# design.net
KiCad netlist of a schematic drawn in Altium Designer
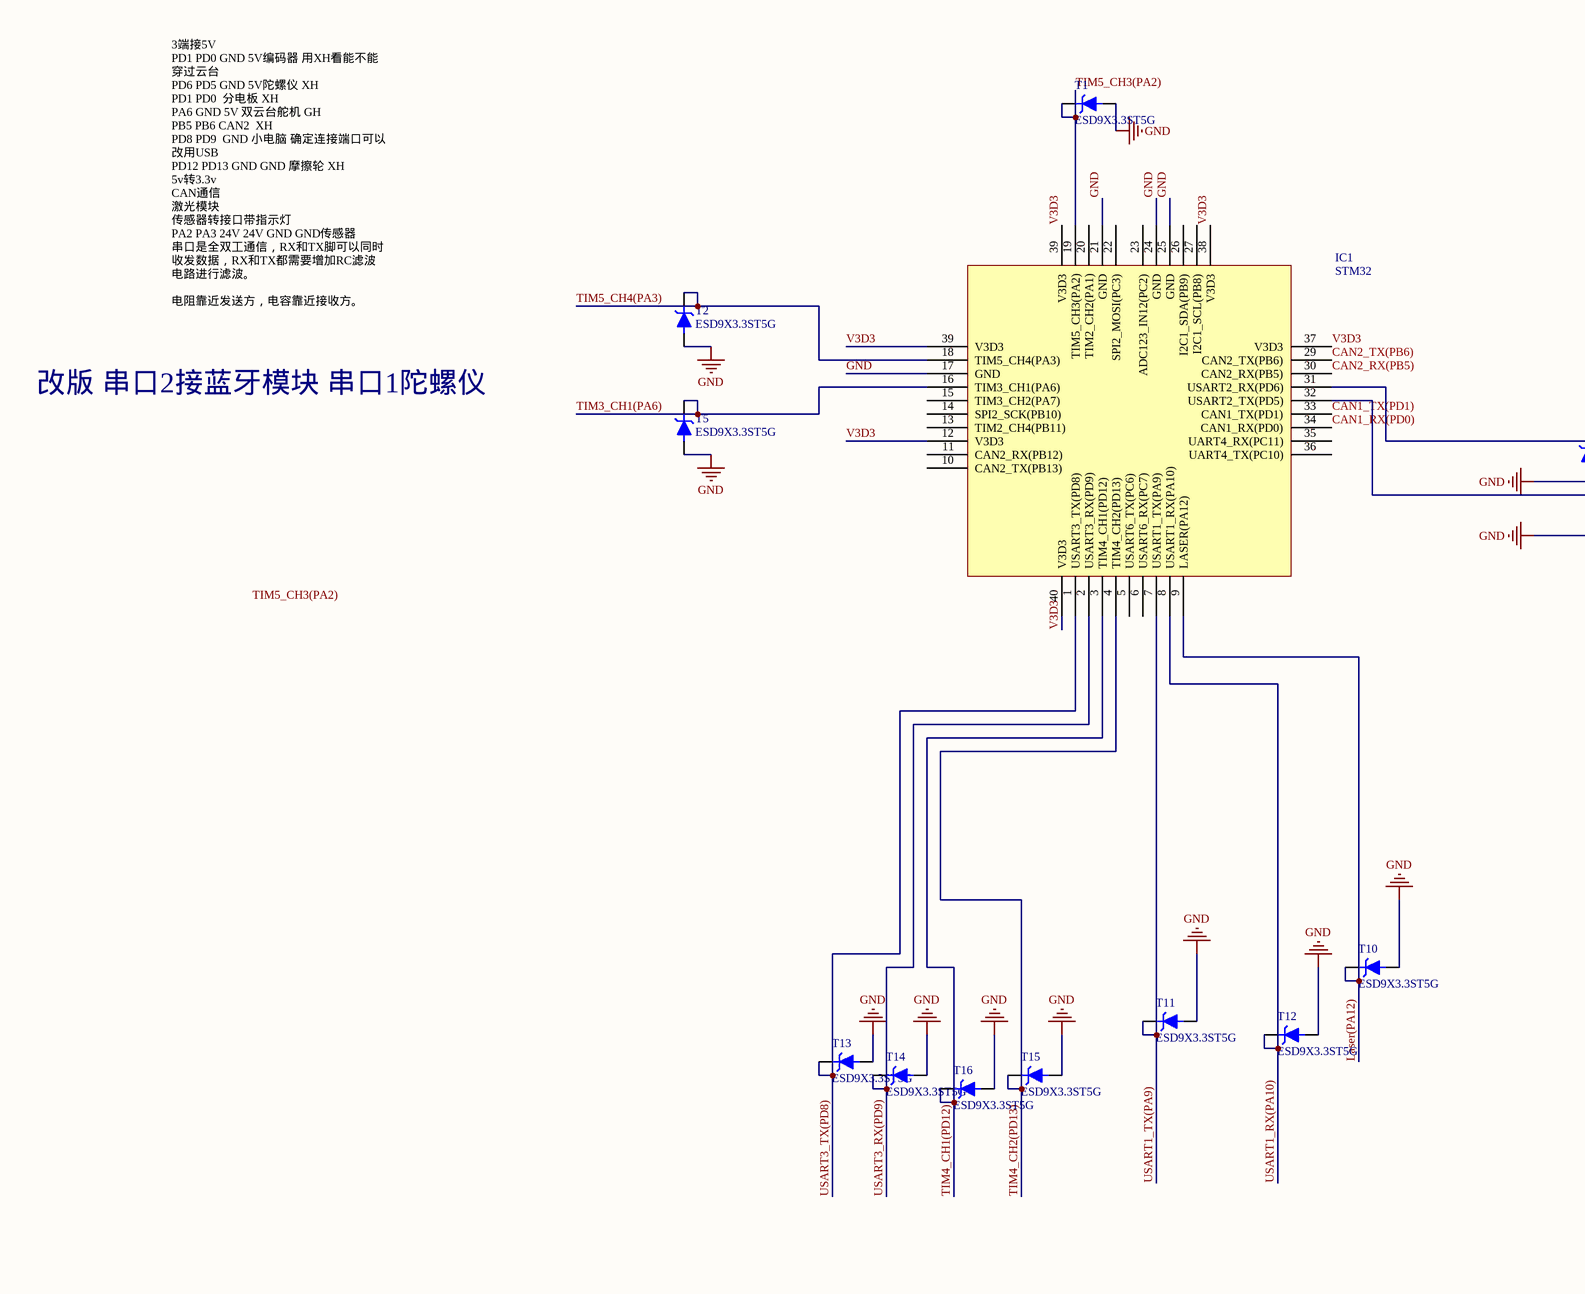
[diagram p0: 云台扩展板.SchDoc, left]
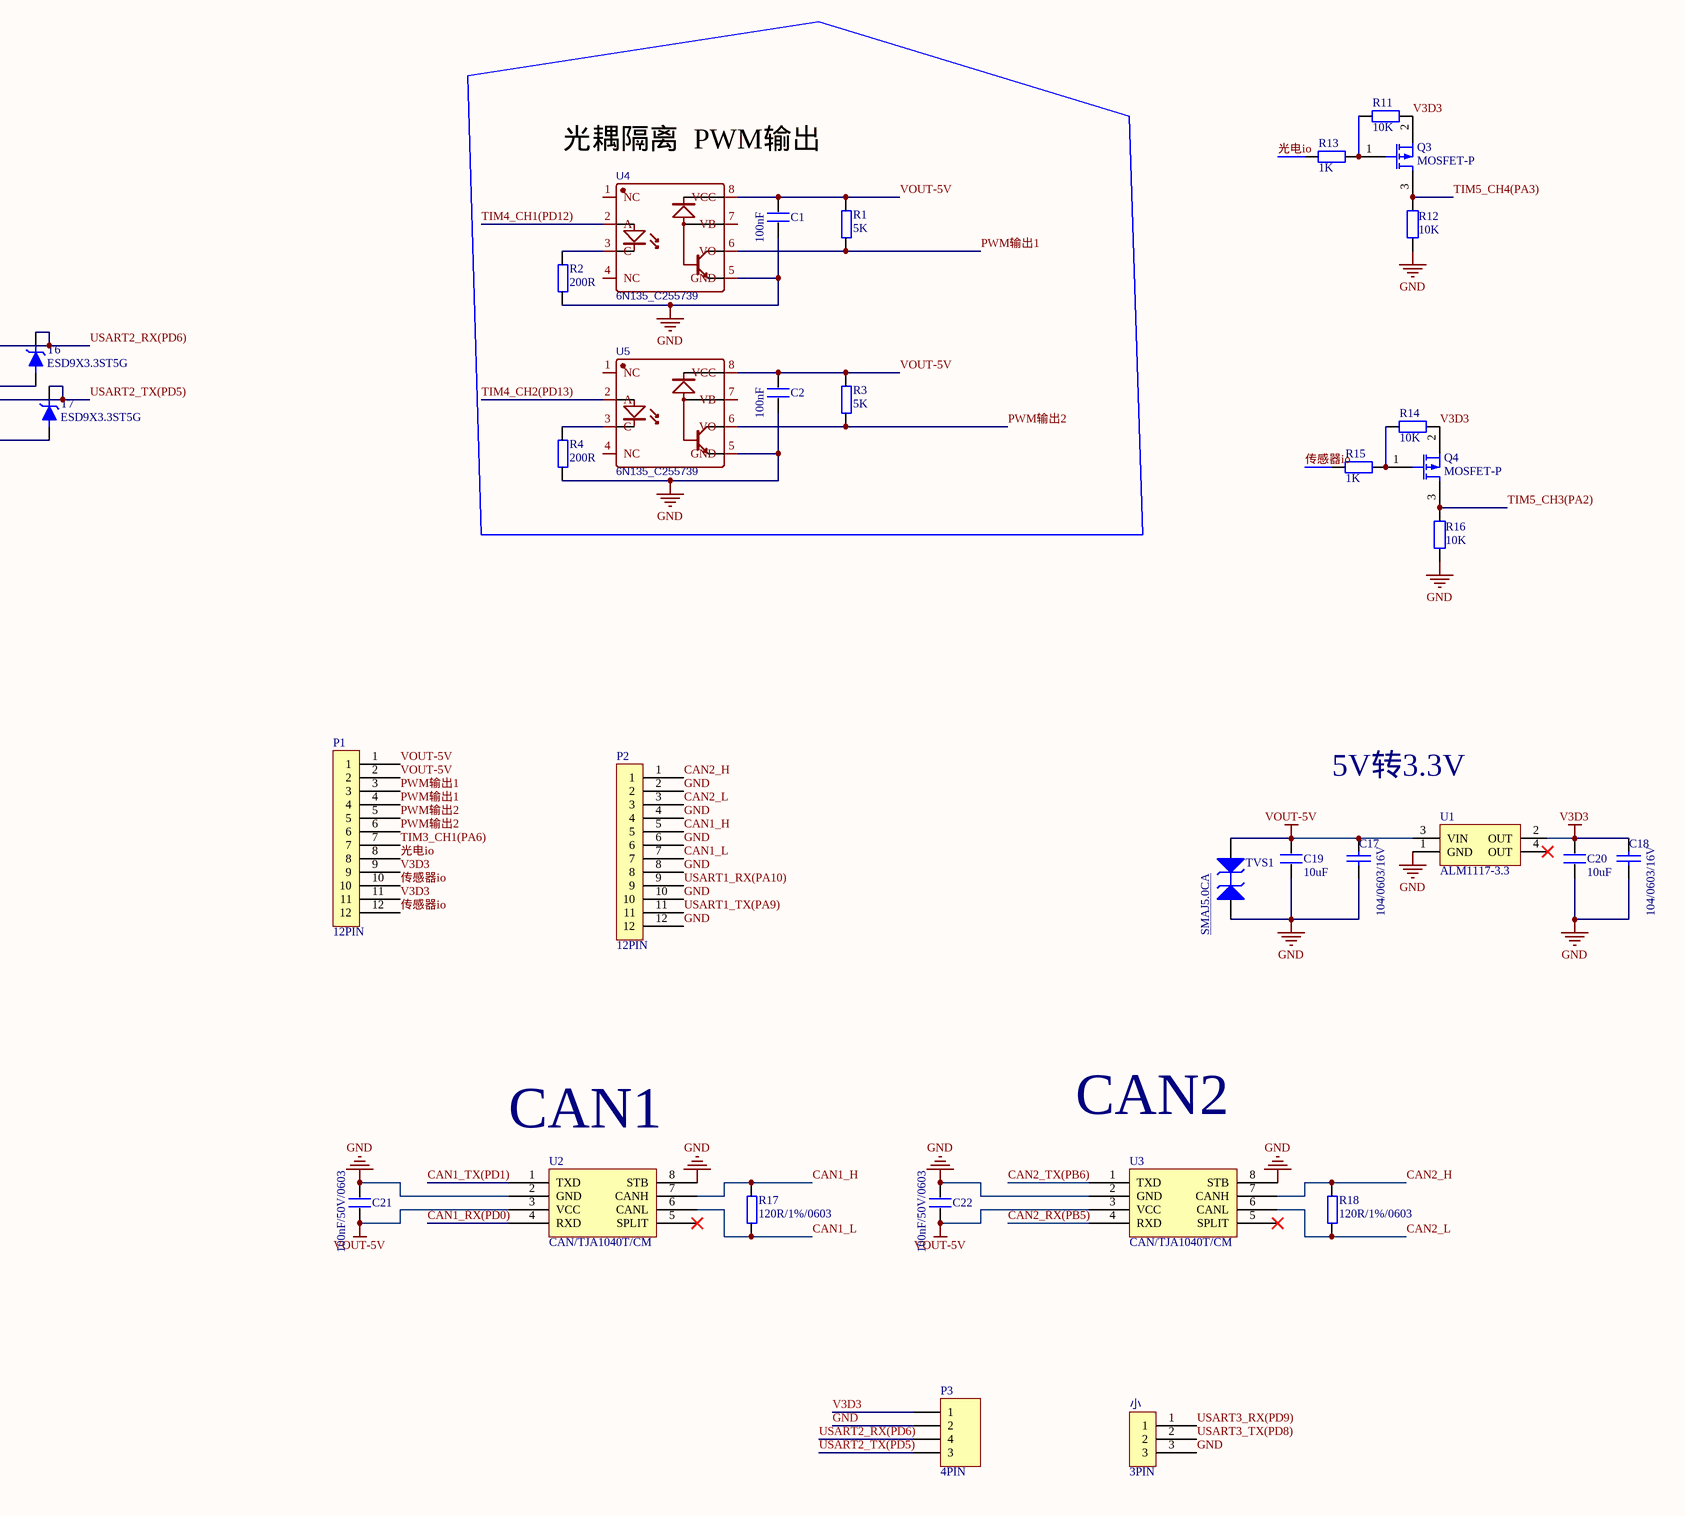
[diagram p1: 云台扩展板.SchDoc, right]

(export (version "E")
  (design (tool "Eeschema 10.0.6"))
  (components
    (comp (ref "C1") (value "100nF") (footprint "0603_C") (libsource (lib "Robotmaster") (part "C")))
    (comp (ref "C2") (value "100nF") (footprint "0603_C") (libsource (lib "Robotmaster") (part "C")))
    (comp (ref "C17")
      (value "104/0603/16V")
      (footprint "C0805")
      (fields (field (name "ALTIUM_UNNAMED_1") "104/0603/16V"))
      (libsource (lib "Common Device") (part "CAP"))
    )
    (comp (ref "C18")
      (value "104/0603/16V")
      (footprint "C0805")
      (fields (field (name "ALTIUM_UNNAMED_1") "104/0603/16V"))
      (libsource (lib "Common Device") (part "CAP"))
    )
    (comp (ref "C19") (value "10uF") (footprint "C0805") (libsource (lib "Robotmaster") (part "C")))
    (comp (ref "C20") (value "10uF") (footprint "C0805") (libsource (lib "Robotmaster") (part "C")))
    (comp (ref "C21") (value "100nF/50V/0603") (footprint "C0805") (libsource (lib "Robotmaster") (part "C")))
    (comp (ref "C22") (value "100nF/50V/0603") (footprint "C0805") (libsource (lib "Robotmaster") (part "C")))
    (comp (ref "IC1") (value "STM32") (footprint "STM") (libsource (lib "PP_SCHlib_Altium") (part "STM32_1")))
    (comp (ref "P1") (value "12PIN") (footprint "12pin") (libsource (lib "更多原理图库") (part "12PIN")))
    (comp (ref "P2") (value "12PIN") (footprint "12pin") (libsource (lib "更多原理图库") (part "12PIN")))
    (comp (ref "P3")
      (value "4PIN")
      (footprint "HDR1X4")
      (description "Header, 4-Pin")
      (fields (field (name "PUBLISHER") "Altium Limited"))
      (libsource (lib "Miscellaneous Connectors") (part "Header 4"))
    )
    (comp (ref "Q3")
      (value "MOSFET-P")
      (footprint "SOT-23(SOT-23-3)")
      (libsource (lib "我的库1.1") (part "MOSFET-P"))
    )
    (comp (ref "Q4")
      (value "MOSFET-P")
      (footprint "SOT-23(SOT-23-3)")
      (libsource (lib "我的库1.1") (part "MOSFET-P"))
    )
    (comp (ref "R1") (value "5K") (footprint "0603_R") (libsource (lib "Robotmaster") (part "R")))
    (comp (ref "R2") (value "200R") (footprint "0603_R") (libsource (lib "Robotmaster") (part "R")))
    (comp (ref "R3") (value "5K") (footprint "0603_R") (libsource (lib "Robotmaster") (part "R")))
    (comp (ref "R4") (value "200R") (footprint "0603_R") (libsource (lib "Robotmaster") (part "R")))
    (comp (ref "R11")
      (value "10K")
      (footprint "0603_R")
      (description "Resistor")
      (fields (field (name "Comment") "Res2"))
      (libsource (lib "我的库") (part "Res2"))
    )
    (comp (ref "R12")
      (value "10K")
      (footprint "0603_R")
      (description "Resistor")
      (fields (field (name "Comment") "Res2"))
      (libsource (lib "") (part "Res2_1"))
    )
    (comp (ref "R13")
      (value "1K")
      (footprint "0603_R")
      (description "Resistor")
      (fields (field (name "Comment") "Res2"))
      (libsource (lib "我的库") (part "Res2"))
    )
    (comp (ref "R14")
      (value "10K")
      (footprint "0603_R")
      (description "Resistor")
      (fields (field (name "Comment") "Res2"))
      (libsource (lib "我的库") (part "Res2"))
    )
    (comp (ref "R15")
      (value "1K")
      (footprint "0603_R")
      (description "Resistor")
      (fields (field (name "Comment") "Res2"))
      (libsource (lib "我的库") (part "Res2"))
    )
    (comp (ref "R16")
      (value "10K")
      (footprint "0603_R")
      (description "Resistor")
      (fields (field (name "Comment") "Res2"))
      (libsource (lib "") (part "Res2_1"))
    )
    (comp (ref "R17") (value "120R/1%/0603") (footprint "0603 R") (libsource (lib "Robotmaster") (part "R")))
    (comp (ref "R18") (value "120R/1%/0603") (footprint "0603 R") (libsource (lib "Robotmaster") (part "R")))
    (comp (ref "T1")
      (value "ESD9X3.3ST5G")
      (footprint "ESD9X3.3ST5G")
      (libsource (lib "PP_SCHlib_Altium") (part "TVS"))
    )
    (comp (ref "T2")
      (value "ESD9X3.3ST5G")
      (footprint "ESD9X3.3ST5G")
      (libsource (lib "PP_SCHlib_Altium") (part "TVS"))
    )
    (comp (ref "T5")
      (value "ESD9X3.3ST5G")
      (footprint "ESD9X3.3ST5G")
      (libsource (lib "PP_SCHlib_Altium") (part "TVS"))
    )
    (comp (ref "T6")
      (value "ESD9X3.3ST5G")
      (footprint "ESD9X3.3ST5G")
      (libsource (lib "PP_SCHlib_Altium") (part "TVS"))
    )
    (comp (ref "T7")
      (value "ESD9X3.3ST5G")
      (footprint "ESD9X3.3ST5G")
      (libsource (lib "PP_SCHlib_Altium") (part "TVS"))
    )
    (comp (ref "T10")
      (value "ESD9X3.3ST5G")
      (footprint "ESD9X3.3ST5G")
      (libsource (lib "PP_SCHlib_Altium") (part "TVS"))
    )
    (comp (ref "T11")
      (value "ESD9X3.3ST5G")
      (footprint "ESD9X3.3ST5G")
      (libsource (lib "PP_SCHlib_Altium") (part "TVS"))
    )
    (comp (ref "T12")
      (value "ESD9X3.3ST5G")
      (footprint "ESD9X3.3ST5G")
      (libsource (lib "PP_SCHlib_Altium") (part "TVS"))
    )
    (comp (ref "T13")
      (value "ESD9X3.3ST5G")
      (footprint "ESD9X3.3ST5G")
      (libsource (lib "PP_SCHlib_Altium") (part "TVS"))
    )
    (comp (ref "T14")
      (value "ESD9X3.3ST5G")
      (footprint "ESD9X3.3ST5G")
      (libsource (lib "PP_SCHlib_Altium") (part "TVS"))
    )
    (comp (ref "T15")
      (value "ESD9X3.3ST5G")
      (footprint "ESD9X3.3ST5G")
      (libsource (lib "PP_SCHlib_Altium") (part "TVS"))
    )
    (comp (ref "T16")
      (value "ESD9X3.3ST5G")
      (footprint "ESD9X3.3ST5G")
      (libsource (lib "PP_SCHlib_Altium") (part "TVS"))
    )
    (comp (ref "TVS1")
      (value "SMAJ5.0CA")
      (footprint "SMA(DO-214AC)_S1")
      (libsource (lib "VL53L0X激光测距传感器模块") (part "TVS"))
    )
    (comp (ref "U1")
      (value "ALM1117-3.3")
      (footprint "SOT-223")
      (libsource (lib "Robotmaster") (part "LM1117-3.3"))
    )
    (comp (ref "U2")
      (value "CAN/TJA1040T/CM")
      (footprint "CAN/TJA1040T/CM")
      (description "CAN")
      (libsource (lib "Miscellaneous Devices LC") (part "CAN/TJA1040T/CM_[C6951]"))
    )
    (comp (ref "U3")
      (value "CAN/TJA1040T/CM")
      (footprint "CAN/TJA1040T/CM")
      (description "CAN")
      (libsource (lib "Miscellaneous Devices LC") (part "CAN/TJA1040T/CM_[C6951]"))
    )
    (comp (ref "U4")
      (value "6N135_C255739")
      (footprint "DIP-8")
      (fields
        (field (name "BOM_SUPPLIER PART") "C255739")
        (field (name "BOM_MANUFACTURER PART") "6N135")
        (field (name "CONTRIBUTOR") "LCSC")
      )
      (libsource (lib "我的库") (part "6N135_C255739"))
    )
    (comp (ref "U5")
      (value "6N135_C255739")
      (footprint "DIP-8")
      (fields
        (field (name "BOM_SUPPLIER PART") "C255739")
        (field (name "BOM_MANUFACTURER PART") "6N135")
        (field (name "CONTRIBUTOR") "LCSC")
      )
      (libsource (lib "我的库") (part "6N135_C255739"))
    )
    (comp (ref "小") (value "3PIN") (footprint "XH2.54-3") (libsource (lib "PP_SCHlib_Altium") (part "3PIN")))
  )
  (nets
    (net (code "1") (name "/CAN1_H") (class "Default")
      (node (ref "P2") (pin "5") (pinfunction "5_5") (pintype "passive"))
      (node (ref "R17") (pin "2") (pintype "passive"))
      (node (ref "U2") (pin "7") (pinfunction "CANH_7") (pintype "passive"))
    )
    (net (code "2") (name "/CAN1_L") (class "Default")
      (node (ref "P2") (pin "7") (pinfunction "7_7") (pintype "passive"))
      (node (ref "R17") (pin "1") (pintype "passive"))
      (node (ref "U2") (pin "6") (pinfunction "CANL_6") (pintype "passive"))
    )
    (net (code "3") (name "/CAN1_RX(PD0)") (class "Default")
      (node (ref "IC1") (pin "34") (pinfunction "CAN1_RX(PD0)_34") (pintype "passive"))
      (node (ref "U2") (pin "4") (pinfunction "RXD_4") (pintype "passive"))
    )
    (net (code "4") (name "/CAN1_TX(PD1)") (class "Default")
      (node (ref "IC1") (pin "33") (pinfunction "CAN1_TX(PD1)_33") (pintype "passive"))
      (node (ref "U2") (pin "1") (pinfunction "TXD_1") (pintype "passive"))
    )
    (net (code "5") (name "/CAN2_H") (class "Default")
      (node (ref "P2") (pin "1") (pinfunction "1_1") (pintype "passive"))
      (node (ref "R18") (pin "2") (pintype "passive"))
      (node (ref "U3") (pin "7") (pinfunction "CANH_7") (pintype "passive"))
    )
    (net (code "6") (name "/CAN2_L") (class "Default")
      (node (ref "P2") (pin "3") (pinfunction "3_3") (pintype "passive"))
      (node (ref "R18") (pin "1") (pintype "passive"))
      (node (ref "U3") (pin "6") (pinfunction "CANL_6") (pintype "passive"))
    )
    (net (code "7") (name "/CAN2_RX(PB5)") (class "Default")
      (node (ref "IC1") (pin "30") (pinfunction "CAN2_RX(PB5)_30") (pintype "passive"))
      (node (ref "U3") (pin "4") (pinfunction "RXD_4") (pintype "passive"))
    )
    (net (code "8") (name "/CAN2_TX(PB6)") (class "Default")
      (node (ref "IC1") (pin "29") (pinfunction "CAN2_TX(PB6)_29") (pintype "passive"))
      (node (ref "U3") (pin "1") (pinfunction "TXD_1") (pintype "passive"))
    )
    (net (code "9") (name "/Laser(PA12)") (class "Default")
      (node (ref "IC1") (pin "9") (pinfunction "LASER(PA12)_9") (pintype "passive"))
      (node (ref "T10") (pin "2") (pinfunction "K_2") (pintype "passive"))
    )
    (net (code "10") (name "/PWM输出1") (class "Default")
      (node (ref "P1") (pin "3") (pinfunction "3_3") (pintype "passive"))
      (node (ref "P1") (pin "4") (pinfunction "4_4") (pintype "passive"))
      (node (ref "R1") (pin "1") (pintype "passive"))
      (node (ref "U4") (pin "6") (pinfunction "VO_6") (pintype "passive"))
    )
    (net (code "11") (name "/PWM输出2") (class "Default")
      (node (ref "P1") (pin "5") (pinfunction "5_5") (pintype "passive"))
      (node (ref "P1") (pin "6") (pinfunction "6_6") (pintype "passive"))
      (node (ref "R3") (pin "1") (pintype "passive"))
      (node (ref "U5") (pin "6") (pinfunction "VO_6") (pintype "passive"))
    )
    (net (code "12") (name "/TIM3_CH1(PA6)") (class "Default")
      (node (ref "IC1") (pin "16") (pinfunction "TIM3_CH1(PA6)_16") (pintype "passive"))
      (node (ref "P1") (pin "7") (pinfunction "7_7") (pintype "passive"))
      (node (ref "T5") (pin "2") (pinfunction "K_2") (pintype "passive"))
    )
    (net (code "13") (name "/TIM4_CH1(PD12)") (class "Default")
      (node (ref "IC1") (pin "3") (pinfunction "TIM4_CH1(PD12)_3") (pintype "passive"))
      (node (ref "T16") (pin "2") (pinfunction "K_2") (pintype "passive"))
      (node (ref "U4") (pin "2") (pinfunction "A_2") (pintype "passive"))
    )
    (net (code "14") (name "/TIM4_CH2(PD13)") (class "Default")
      (node (ref "IC1") (pin "4") (pinfunction "TIM4_CH2(PD13)_4") (pintype "passive"))
      (node (ref "T15") (pin "2") (pinfunction "K_2") (pintype "passive"))
      (node (ref "U5") (pin "2") (pinfunction "A_2") (pintype "passive"))
    )
    (net (code "15") (name "/TIM5_CH3(PA2)") (class "Default")
      (node (ref "IC1") (pin "19") (pinfunction "TIM5_CH3(PA2)_19") (pintype "passive"))
      (node (ref "Q4") (pin "3") (pinfunction "D_3") (pintype "passive"))
      (node (ref "R16") (pin "1") (pinfunction "1_1") (pintype "passive"))
      (node (ref "T1") (pin "2") (pinfunction "K_2") (pintype "passive"))
    )
    (net (code "16") (name "/TIM5_CH4(PA3)") (class "Default")
      (node (ref "IC1") (pin "18") (pinfunction "TIM5_CH4(PA3)_18") (pintype "passive"))
      (node (ref "Q3") (pin "3") (pinfunction "D_3") (pintype "passive"))
      (node (ref "R12") (pin "1") (pinfunction "1_1") (pintype "passive"))
      (node (ref "T2") (pin "2") (pinfunction "K_2") (pintype "passive"))
    )
    (net (code "17") (name "/USART1_RX(PA10)") (class "Default")
      (node (ref "IC1") (pin "8") (pinfunction "USART1_RX(PA10)_8") (pintype "passive"))
      (node (ref "P2") (pin "9") (pinfunction "9_9") (pintype "passive"))
      (node (ref "T12") (pin "2") (pinfunction "K_2") (pintype "passive"))
    )
    (net (code "18") (name "/USART1_TX(PA9)") (class "Default")
      (node (ref "IC1") (pin "7") (pinfunction "USART1_TX(PA9)_7") (pintype "passive"))
      (node (ref "P2") (pin "11") (pinfunction "11_11") (pintype "passive"))
      (node (ref "T11") (pin "2") (pinfunction "K_2") (pintype "passive"))
    )
    (net (code "19") (name "/USART2_RX(PD6)") (class "Default")
      (node (ref "IC1") (pin "31") (pinfunction "USART2_RX(PD6)_31") (pintype "passive"))
      (node (ref "P3") (pin "4") (pinfunction "4_4") (pintype "passive"))
      (node (ref "T6") (pin "2") (pinfunction "K_2") (pintype "passive"))
    )
    (net (code "20") (name "/USART2_TX(PD5)") (class "Default")
      (node (ref "IC1") (pin "32") (pinfunction "USART2_TX(PD5)_32") (pintype "passive"))
      (node (ref "P3") (pin "3") (pinfunction "3_3") (pintype "passive"))
      (node (ref "T7") (pin "2") (pinfunction "K_2") (pintype "passive"))
    )
    (net (code "21") (name "/USART3_RX(PD9)") (class "Default")
      (node (ref "IC1") (pin "2") (pinfunction "USART3_RX(PD9)_2") (pintype "passive"))
      (node (ref "T14") (pin "2") (pinfunction "K_2") (pintype "passive"))
      (node (ref "小") (pin "1") (pinfunction "1_1") (pintype "passive"))
    )
    (net (code "22") (name "/USART3_TX(PD8)") (class "Default")
      (node (ref "IC1") (pin "1") (pinfunction "USART3_TX(PD8)_1") (pintype "passive"))
      (node (ref "T13") (pin "2") (pinfunction "K_2") (pintype "passive"))
      (node (ref "小") (pin "2") (pinfunction "2_2") (pintype "passive"))
    )
    (net (code "23") (name "/传感器io") (class "Default")
      (node (ref "P1") (pin "10") (pinfunction "10_10") (pintype "passive"))
      (node (ref "P1") (pin "12") (pinfunction "12_12") (pintype "passive"))
      (node (ref "R15") (pin "2") (pinfunction "2_2") (pintype "passive"))
    )
    (net (code "24") (name "/光电io") (class "Default")
      (node (ref "P1") (pin "8") (pinfunction "8_8") (pintype "passive"))
      (node (ref "R13") (pin "2") (pinfunction "2_2") (pintype "passive"))
    )
    (net (code "25") (name "GND") (class "Default")
      (node (ref "C1") (pin "1") (pintype "passive"))
      (node (ref "C17") (pin "1") (pinfunction "1_1") (pintype "passive"))
      (node (ref "C18") (pin "1") (pinfunction "1_1") (pintype "passive"))
      (node (ref "C19") (pin "1") (pintype "passive"))
      (node (ref "C2") (pin "1") (pintype "passive"))
      (node (ref "C20") (pin "1") (pintype "passive"))
      (node (ref "C21") (pin "2") (pintype "passive"))
      (node (ref "C22") (pin "2") (pintype "passive"))
      (node (ref "IC1") (pin "17") (pinfunction "GND_17") (pintype "passive"))
      (node (ref "IC1") (pin "21") (pinfunction "GND_21") (pintype "passive"))
      (node (ref "IC1") (pin "24") (pinfunction "GND_24") (pintype "passive"))
      (node (ref "IC1") (pin "25") (pinfunction "GND_25") (pintype "passive"))
      (node (ref "P2") (pin "10") (pinfunction "10_10") (pintype "passive"))
      (node (ref "P2") (pin "12") (pinfunction "12_12") (pintype "passive"))
      (node (ref "P2") (pin "2") (pinfunction "2_2") (pintype "passive"))
      (node (ref "P2") (pin "4") (pinfunction "4_4") (pintype "passive"))
      (node (ref "P2") (pin "6") (pinfunction "6_6") (pintype "passive"))
      (node (ref "P2") (pin "8") (pinfunction "8_8") (pintype "passive"))
      (node (ref "P3") (pin "2") (pinfunction "2_2") (pintype "passive"))
      (node (ref "R12") (pin "2") (pinfunction "2_2") (pintype "passive"))
      (node (ref "R16") (pin "2") (pinfunction "2_2") (pintype "passive"))
      (node (ref "R2") (pin "1") (pintype "passive"))
      (node (ref "R4") (pin "1") (pintype "passive"))
      (node (ref "T1") (pin "1") (pinfunction "A_1") (pintype "passive"))
      (node (ref "T10") (pin "1") (pinfunction "A_1") (pintype "passive"))
      (node (ref "T11") (pin "1") (pinfunction "A_1") (pintype "passive"))
      (node (ref "T12") (pin "1") (pinfunction "A_1") (pintype "passive"))
      (node (ref "T13") (pin "1") (pinfunction "A_1") (pintype "passive"))
      (node (ref "T14") (pin "1") (pinfunction "A_1") (pintype "passive"))
      (node (ref "T15") (pin "1") (pinfunction "A_1") (pintype "passive"))
      (node (ref "T16") (pin "1") (pinfunction "A_1") (pintype "passive"))
      (node (ref "T2") (pin "1") (pinfunction "A_1") (pintype "passive"))
      (node (ref "T5") (pin "1") (pinfunction "A_1") (pintype "passive"))
      (node (ref "T6") (pin "1") (pinfunction "A_1") (pintype "passive"))
      (node (ref "T7") (pin "1") (pinfunction "A_1") (pintype "passive"))
      (node (ref "TVS1") (pin "1") (pinfunction "A_1") (pintype "passive"))
      (node (ref "U1") (pin "1") (pinfunction "GND_1") (pintype "passive"))
      (node (ref "U2") (pin "2") (pinfunction "GND_2") (pintype "passive"))
      (node (ref "U2") (pin "8") (pinfunction "STB_8") (pintype "passive"))
      (node (ref "U3") (pin "2") (pinfunction "GND_2") (pintype "passive"))
      (node (ref "U3") (pin "8") (pinfunction "STB_8") (pintype "passive"))
      (node (ref "U4") (pin "5") (pinfunction "GND_5") (pintype "passive"))
      (node (ref "U5") (pin "5") (pinfunction "GND_5") (pintype "passive"))
      (node (ref "小") (pin "3") (pinfunction "3_3") (pintype "passive"))
    )
    (net (code "26") (name "Net-(Q3-G)") (class "Default")
      (node (ref "Q3") (pin "1") (pinfunction "G_1") (pintype "passive"))
      (node (ref "R11") (pin "2") (pinfunction "2_2") (pintype "passive"))
      (node (ref "R13") (pin "1") (pinfunction "1_1") (pintype "passive"))
    )
    (net (code "27") (name "Net-(Q4-G)") (class "Default")
      (node (ref "Q4") (pin "1") (pinfunction "G_1") (pintype "passive"))
      (node (ref "R14") (pin "2") (pinfunction "2_2") (pintype "passive"))
      (node (ref "R15") (pin "1") (pinfunction "1_1") (pintype "passive"))
    )
    (net (code "28") (name "Net-(U4-C)") (class "Default")
      (node (ref "R2") (pin "2") (pintype "passive"))
      (node (ref "U4") (pin "3") (pinfunction "C_3") (pintype "passive"))
    )
    (net (code "29") (name "Net-(U5-C)") (class "Default")
      (node (ref "R4") (pin "2") (pintype "passive"))
      (node (ref "U5") (pin "3") (pinfunction "C_3") (pintype "passive"))
    )
    (net (code "30") (name "V3D3") (class "Default")
      (node (ref "C18") (pin "2") (pinfunction "2_2") (pintype "passive"))
      (node (ref "C20") (pin "2") (pintype "passive"))
      (node (ref "IC1") (pin "12") (pinfunction "V3D3_12") (pintype "passive"))
      (node (ref "IC1") (pin "37") (pinfunction "V3D3_37") (pintype "passive"))
      (node (ref "IC1") (pin "38") (pinfunction "V3D3_38") (pintype "passive"))
      (node (ref "IC1") (pin "39") (pinfunction "V3D3_39") (pintype "passive"))
      (node (ref "IC1") (pin "40") (pinfunction "V3D3_40") (pintype "passive"))
      (node (ref "P1") (pin "11") (pinfunction "11_11") (pintype "passive"))
      (node (ref "P1") (pin "9") (pinfunction "9_9") (pintype "passive"))
      (node (ref "P3") (pin "1") (pinfunction "1_1") (pintype "passive"))
      (node (ref "Q3") (pin "2") (pinfunction "S_2") (pintype "passive"))
      (node (ref "Q4") (pin "2") (pinfunction "S_2") (pintype "passive"))
      (node (ref "R11") (pin "1") (pinfunction "1_1") (pintype "passive"))
      (node (ref "R14") (pin "1") (pinfunction "1_1") (pintype "passive"))
      (node (ref "U1") (pin "2") (pinfunction "OUT_2") (pintype "passive"))
    )
    (net (code "31") (name "VOUT-5V") (class "Default")
      (node (ref "C1") (pin "2") (pintype "passive"))
      (node (ref "C17") (pin "2") (pinfunction "2_2") (pintype "passive"))
      (node (ref "C19") (pin "2") (pintype "passive"))
      (node (ref "C2") (pin "2") (pintype "passive"))
      (node (ref "C21") (pin "1") (pintype "passive"))
      (node (ref "C22") (pin "1") (pintype "passive"))
      (node (ref "P1") (pin "1") (pinfunction "1_1") (pintype "passive"))
      (node (ref "P1") (pin "2") (pinfunction "2_2") (pintype "passive"))
      (node (ref "R1") (pin "2") (pintype "passive"))
      (node (ref "R3") (pin "2") (pintype "passive"))
      (node (ref "TVS1") (pin "2") (pinfunction "K_2") (pintype "passive"))
      (node (ref "U1") (pin "3") (pinfunction "VIN_3") (pintype "passive"))
      (node (ref "U2") (pin "3") (pinfunction "VCC_3") (pintype "passive"))
      (node (ref "U3") (pin "3") (pinfunction "VCC_3") (pintype "passive"))
      (node (ref "U4") (pin "8") (pinfunction "VCC_8") (pintype "passive"))
      (node (ref "U5") (pin "8") (pinfunction "VCC_8") (pintype "passive"))
    )
    (net (code "32") (name "unconnected-(IC1-ADC123_IN12(PC2)-Pad23)") (class "Default")
      (node (ref "IC1") (pin "23") (pinfunction "ADC123_IN12(PC2)_23") (pintype "passive"))
    )
    (net (code "33") (name "unconnected-(IC1-CAN2_RX(PB12)-Pad11)") (class "Default")
      (node (ref "IC1") (pin "11") (pinfunction "CAN2_RX(PB12)_11") (pintype "passive"))
    )
    (net (code "34") (name "unconnected-(IC1-CAN2_TX(PB13)-Pad10)") (class "Default")
      (node (ref "IC1") (pin "10") (pinfunction "CAN2_TX(PB13)_10") (pintype "passive"))
    )
    (net (code "35") (name "unconnected-(IC1-I2C1_SCL(PB8)-Pad27)") (class "Default")
      (node (ref "IC1") (pin "27") (pinfunction "I2C1_SCL(PB8)_27") (pintype "passive"))
    )
    (net (code "36") (name "unconnected-(IC1-I2C1_SDA(PB9)-Pad26)") (class "Default")
      (node (ref "IC1") (pin "26") (pinfunction "I2C1_SDA(PB9)_26") (pintype "passive"))
    )
    (net (code "37") (name "unconnected-(IC1-SPI2_MOSI(PC3)-Pad22)") (class "Default")
      (node (ref "IC1") (pin "22") (pinfunction "SPI2_MOSI(PC3)_22") (pintype "passive"))
    )
    (net (code "38") (name "unconnected-(IC1-SPI2_SCK(PB10)-Pad14)") (class "Default")
      (node (ref "IC1") (pin "14") (pinfunction "SPI2_SCK(PB10)_14") (pintype "passive"))
    )
    (net (code "39") (name "unconnected-(IC1-TIM2_CH2(PA1)-Pad20)") (class "Default")
      (node (ref "IC1") (pin "20") (pinfunction "TIM2_CH2(PA1)_20") (pintype "passive"))
    )
    (net (code "40") (name "unconnected-(IC1-TIM2_CH4(PB11)-Pad13)") (class "Default")
      (node (ref "IC1") (pin "13") (pinfunction "TIM2_CH4(PB11)_13") (pintype "passive"))
    )
    (net (code "41") (name "unconnected-(IC1-TIM3_CH2(PA7)-Pad15)") (class "Default")
      (node (ref "IC1") (pin "15") (pinfunction "TIM3_CH2(PA7)_15") (pintype "passive"))
    )
    (net (code "42") (name "unconnected-(IC1-UART4_RX(PC11)-Pad35)") (class "Default")
      (node (ref "IC1") (pin "35") (pinfunction "UART4_RX(PC11)_35") (pintype "passive"))
    )
    (net (code "43") (name "unconnected-(IC1-UART4_TX(PC10)-Pad36)") (class "Default")
      (node (ref "IC1") (pin "36") (pinfunction "UART4_TX(PC10)_36") (pintype "passive"))
    )
    (net (code "44") (name "unconnected-(IC1-USART6_RX(PC7)-Pad6)") (class "Default")
      (node (ref "IC1") (pin "6") (pinfunction "USART6_RX(PC7)_6") (pintype "passive"))
    )
    (net (code "45") (name "unconnected-(IC1-USART6_TX(PC6)-Pad5)") (class "Default")
      (node (ref "IC1") (pin "5") (pinfunction "USART6_TX(PC6)_5") (pintype "passive"))
    )
    (net (code "46") (name "unconnected-(U1-OUT-Pad4)") (class "Default")
      (node (ref "U1") (pin "4") (pinfunction "OUT_4") (pintype "passive+no_connect"))
    )
    (net (code "47") (name "unconnected-(U2-SPLIT-Pad5)") (class "Default")
      (node (ref "U2") (pin "5") (pinfunction "SPLIT_5") (pintype "passive+no_connect"))
    )
    (net (code "48") (name "unconnected-(U3-SPLIT-Pad5)") (class "Default")
      (node (ref "U3") (pin "5") (pinfunction "SPLIT_5") (pintype "passive+no_connect"))
    )
    (net (code "49") (name "unconnected-(U4-NC-Pad1)") (class "Default")
      (node (ref "U4") (pin "1") (pinfunction "NC_1") (pintype "passive"))
    )
    (net (code "50") (name "unconnected-(U4-NC-Pad4)") (class "Default")
      (node (ref "U4") (pin "4") (pinfunction "NC_4") (pintype "passive"))
    )
    (net (code "51") (name "unconnected-(U4-VB-Pad7)") (class "Default")
      (node (ref "U4") (pin "7") (pinfunction "VB_7") (pintype "passive"))
    )
    (net (code "52") (name "unconnected-(U5-NC-Pad1)") (class "Default")
      (node (ref "U5") (pin "1") (pinfunction "NC_1") (pintype "passive"))
    )
    (net (code "53") (name "unconnected-(U5-NC-Pad4)") (class "Default")
      (node (ref "U5") (pin "4") (pinfunction "NC_4") (pintype "passive"))
    )
    (net (code "54") (name "unconnected-(U5-VB-Pad7)") (class "Default")
      (node (ref "U5") (pin "7") (pinfunction "VB_7") (pintype "passive"))
    )
  )
)
